# tester.net
KiCad netlist of a schematic drawn in EAGLE
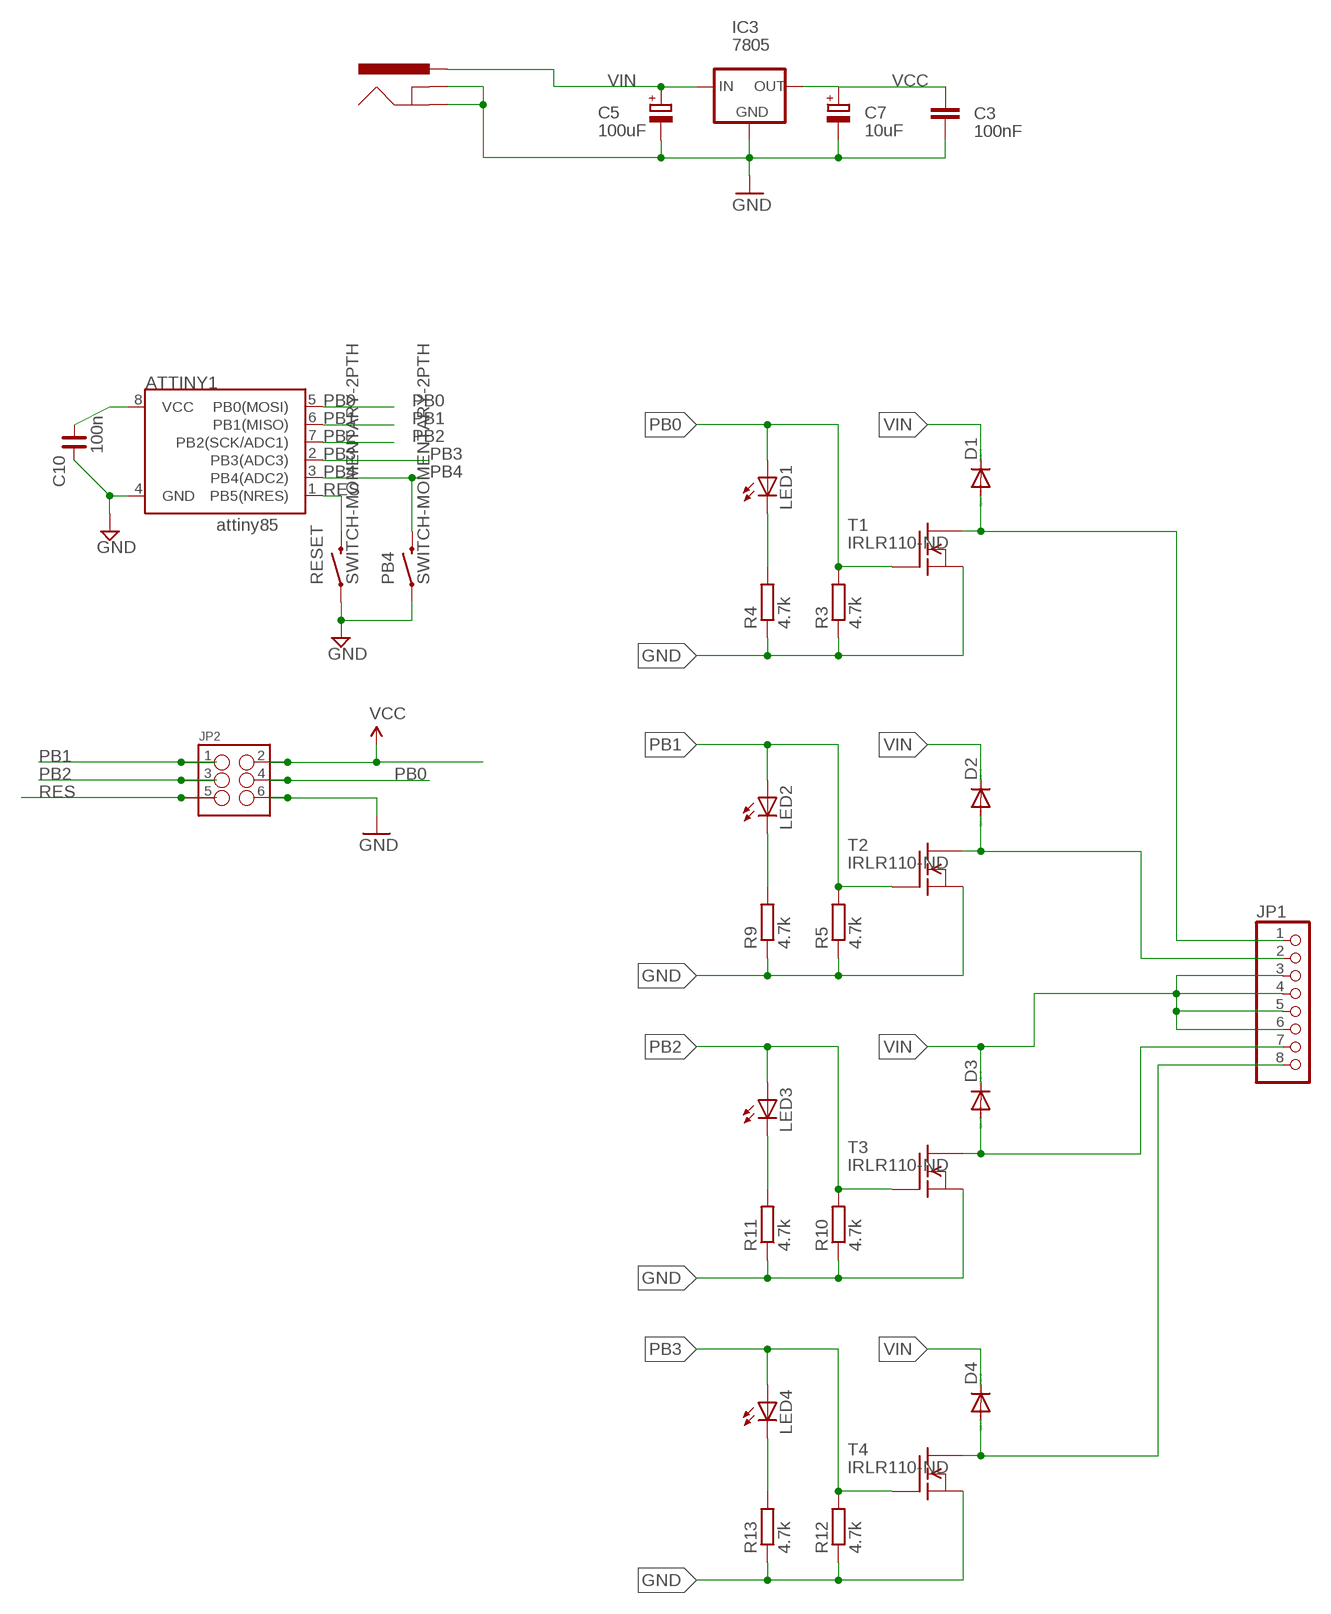
[diagram p0: schematic, sheet 1]

(export (version "E")
  (design (tool "Eeschema 10.0.6"))
  (components
    (comp (ref "ATTINY1")
      (value "ATTINY45DIP8")
      (footprint "eagle-import:DIP08")
      (libsource (lib "eagle-import") (part "ATTINY45DIP8"))
    )
    (comp (ref "C3")
      (value "100nF")
      (footprint "eagle-import:C050-024X044")
      (libsource (lib "eagle-import") (part "C-EU050-024X044"))
    )
    (comp (ref "C5")
      (value "100uF")
      (footprint "eagle-import:E2,5-5")
      (libsource (lib "eagle-import") (part "CPOL-EUE2.5-5"))
    )
    (comp (ref "C7")
      (value "10uF")
      (footprint "eagle-import:E2,5-5")
      (libsource (lib "eagle-import") (part "CPOL-EUE2.5-5"))
    )
    (comp (ref "C10")
      (value "100n")
      (footprint "eagle-import:C0603")
      (libsource (lib "eagle-import") (part "C_0603"))
    )
    (comp (ref "D1")
      (value "DIODE-DO214AC")
      (footprint "eagle-import:DO214AC")
      (libsource (lib "eagle-import") (part "DIODE-DO214AC"))
    )
    (comp (ref "D2")
      (value "DIODE-DO214AC")
      (footprint "eagle-import:DO214AC")
      (libsource (lib "eagle-import") (part "DIODE-DO214AC"))
    )
    (comp (ref "D3")
      (value "DIODE-DO214AC")
      (footprint "eagle-import:DO214AC")
      (libsource (lib "eagle-import") (part "DIODE-DO214AC"))
    )
    (comp (ref "D4")
      (value "DIODE-DO214AC")
      (footprint "eagle-import:DO214AC")
      (libsource (lib "eagle-import") (part "DIODE-DO214AC"))
    )
    (comp (ref "IC3")
      (value "7805")
      (footprint "eagle-import:78XXL")
      (libsource (lib "eagle-import") (part "78XXL"))
    )
    (comp (ref "J16")
      (value "POWER_JACKPTH")
      (footprint "eagle-import:POWER_JACK_PTH")
      (libsource (lib "eagle-import") (part "POWER_JACKPTH"))
    )
    (comp (ref "JP1")
      (value "PINHD-1X8")
      (footprint "eagle-import:1X08")
      (libsource (lib "eagle-import") (part "PINHD-1X8"))
    )
    (comp (ref "JP2")
      (value "M03X2NO_SILK")
      (footprint "eagle-import:2X3-NS@1")
      (libsource (lib "eagle-import") (part "M03X2NO_SILK"))
    )
    (comp (ref "LED1")
      (value "LEDCHIPLED_1206")
      (footprint "eagle-import:CHIPLED_1206")
      (libsource (lib "eagle-import") (part "LEDCHIPLED_1206"))
    )
    (comp (ref "LED2")
      (value "LEDCHIPLED_1206")
      (footprint "eagle-import:CHIPLED_1206")
      (libsource (lib "eagle-import") (part "LEDCHIPLED_1206"))
    )
    (comp (ref "LED3")
      (value "LEDCHIPLED_1206")
      (footprint "eagle-import:CHIPLED_1206")
      (libsource (lib "eagle-import") (part "LEDCHIPLED_1206"))
    )
    (comp (ref "LED4")
      (value "LEDCHIPLED_1206")
      (footprint "eagle-import:CHIPLED_1206")
      (libsource (lib "eagle-import") (part "LEDCHIPLED_1206"))
    )
    (comp (ref "PB4")
      (value "SWITCH-MOMENTARY-2PTH")
      (footprint "eagle-import:TACTILE-PTH")
      (libsource (lib "eagle-import") (part "SWITCH-MOMENTARY-2PTH"))
    )
    (comp (ref "R3")
      (value "4.7k")
      (footprint "eagle-import:R0603")
      (libsource (lib "eagle-import") (part "R-EU_R0603"))
    )
    (comp (ref "R4")
      (value "4.7k")
      (footprint "eagle-import:R0603")
      (libsource (lib "eagle-import") (part "R-EU_R0603"))
    )
    (comp (ref "R5")
      (value "4.7k")
      (footprint "eagle-import:R0603")
      (libsource (lib "eagle-import") (part "R-EU_R0603"))
    )
    (comp (ref "R9")
      (value "4.7k")
      (footprint "eagle-import:R0603")
      (libsource (lib "eagle-import") (part "R-EU_R0603"))
    )
    (comp (ref "R10")
      (value "4.7k")
      (footprint "eagle-import:R0603")
      (libsource (lib "eagle-import") (part "R-EU_R0603"))
    )
    (comp (ref "R11")
      (value "4.7k")
      (footprint "eagle-import:R0603")
      (libsource (lib "eagle-import") (part "R-EU_R0603"))
    )
    (comp (ref "R12")
      (value "4.7k")
      (footprint "eagle-import:R0603")
      (libsource (lib "eagle-import") (part "R-EU_R0603"))
    )
    (comp (ref "R13")
      (value "4.7k")
      (footprint "eagle-import:R0603")
      (libsource (lib "eagle-import") (part "R-EU_R0603"))
    )
    (comp (ref "RESET")
      (value "SWITCH-MOMENTARY-2PTH")
      (footprint "eagle-import:TACTILE-PTH")
      (libsource (lib "eagle-import") (part "SWITCH-MOMENTARY-2PTH"))
    )
    (comp (ref "T1")
      (value "IRLR110-ND")
      (footprint "eagle-import:TO252")
      (libsource (lib "eagle-import") (part "IRLR110-ND"))
    )
    (comp (ref "T2")
      (value "IRLR110-ND")
      (footprint "eagle-import:TO252")
      (libsource (lib "eagle-import") (part "IRLR110-ND"))
    )
    (comp (ref "T3")
      (value "IRLR110-ND")
      (footprint "eagle-import:TO252")
      (libsource (lib "eagle-import") (part "IRLR110-ND"))
    )
    (comp (ref "T4")
      (value "IRLR110-ND")
      (footprint "eagle-import:TO252")
      (libsource (lib "eagle-import") (part "IRLR110-ND"))
    )
  )
  (nets
    (net (code "1") (name "/PB4") (class "Default")
      (node (ref "ATTINY1") (pin "3") (pinfunction "PB4(ADC2)_3") (pintype "bidirectional"))
      (node (ref "PB4") (pin "3") (pinfunction "2_3") (pintype "passive"))
    )
    (net (code "2") (name "/RES") (class "Default")
      (node (ref "ATTINY1") (pin "1") (pinfunction "PB5(NRES)_1") (pintype "bidirectional"))
      (node (ref "JP2") (pin "5") (pinfunction "5_5") (pintype "bidirectional"))
      (node (ref "RESET") (pin "3") (pinfunction "2_3") (pintype "passive"))
    )
    (net (code "3") (name "GND") (class "Default")
      (node (ref "ATTINY1") (pin "4") (pinfunction "GND_4") (pintype "bidirectional"))
      (node (ref "C10") (pin "2") (pinfunction "2_2") (pintype "passive"))
      (node (ref "C3") (pin "2") (pinfunction "2_2") (pintype "passive"))
      (node (ref "C5") (pin "-") (pinfunction "-_-") (pintype "passive"))
      (node (ref "C7") (pin "-") (pinfunction "-_-") (pintype "passive"))
      (node (ref "IC3") (pin "GND") (pinfunction "GND_GND") (pintype "input"))
      (node (ref "J16") (pin "GND") (pinfunction "GND_GND") (pintype "bidirectional"))
      (node (ref "J16") (pin "GNDBREAK") (pinfunction "GNDBREAK_GNDBREAK") (pintype "bidirectional"))
      (node (ref "JP2") (pin "6") (pinfunction "6_6") (pintype "bidirectional"))
      (node (ref "PB4") (pin "1") (pinfunction "1_1") (pintype "passive"))
      (node (ref "R10") (pin "1") (pinfunction "1_1") (pintype "passive"))
      (node (ref "R11") (pin "1") (pinfunction "1_1") (pintype "passive"))
      (node (ref "R12") (pin "1") (pinfunction "1_1") (pintype "passive"))
      (node (ref "R13") (pin "1") (pinfunction "1_1") (pintype "passive"))
      (node (ref "R3") (pin "1") (pinfunction "1_1") (pintype "passive"))
      (node (ref "R4") (pin "1") (pinfunction "1_1") (pintype "passive"))
      (node (ref "R5") (pin "1") (pinfunction "1_1") (pintype "passive"))
      (node (ref "R9") (pin "1") (pinfunction "1_1") (pintype "passive"))
      (node (ref "RESET") (pin "1") (pinfunction "1_1") (pintype "passive"))
      (node (ref "T1") (pin "2") (pinfunction "S_2") (pintype "passive"))
      (node (ref "T2") (pin "2") (pinfunction "S_2") (pintype "passive"))
      (node (ref "T3") (pin "2") (pinfunction "S_2") (pintype "passive"))
      (node (ref "T4") (pin "2") (pinfunction "S_2") (pintype "passive"))
    )
    (net (code "4") (name "Net-(LED1-PadC)") (class "Default")
      (node (ref "LED1") (pin "C") (pinfunction "C_C") (pintype "passive"))
      (node (ref "R4") (pin "2") (pinfunction "2_2") (pintype "passive"))
    )
    (net (code "5") (name "Net-(LED2-PadC)") (class "Default")
      (node (ref "LED2") (pin "C") (pinfunction "C_C") (pintype "passive"))
      (node (ref "R9") (pin "2") (pinfunction "2_2") (pintype "passive"))
    )
    (net (code "6") (name "Net-(LED3-PadC)") (class "Default")
      (node (ref "LED3") (pin "C") (pinfunction "C_C") (pintype "passive"))
      (node (ref "R11") (pin "2") (pinfunction "2_2") (pintype "passive"))
    )
    (net (code "7") (name "Net-(LED4-PadC)") (class "Default")
      (node (ref "LED4") (pin "C") (pinfunction "C_C") (pintype "passive"))
      (node (ref "R13") (pin "2") (pinfunction "2_2") (pintype "passive"))
    )
    (net (code "8") (name "Net-(T1-D)") (class "Default")
      (node (ref "D1") (pin "A") (pinfunction "A_A") (pintype "passive"))
      (node (ref "JP1") (pin "1") (pinfunction "1_1") (pintype "passive"))
      (node (ref "T1") (pin "3") (pinfunction "D_3") (pintype "passive"))
    )
    (net (code "9") (name "Net-(T2-D)") (class "Default")
      (node (ref "D2") (pin "A") (pinfunction "A_A") (pintype "passive"))
      (node (ref "JP1") (pin "2") (pinfunction "2_2") (pintype "passive"))
      (node (ref "T2") (pin "3") (pinfunction "D_3") (pintype "passive"))
    )
    (net (code "10") (name "Net-(T3-D)") (class "Default")
      (node (ref "D3") (pin "A") (pinfunction "A_A") (pintype "passive"))
      (node (ref "JP1") (pin "7") (pinfunction "7_7") (pintype "passive"))
      (node (ref "T3") (pin "3") (pinfunction "D_3") (pintype "passive"))
    )
    (net (code "11") (name "Net-(T4-D)") (class "Default")
      (node (ref "D4") (pin "A") (pinfunction "A_A") (pintype "passive"))
      (node (ref "JP1") (pin "8") (pinfunction "8_8") (pintype "passive"))
      (node (ref "T4") (pin "3") (pinfunction "D_3") (pintype "passive"))
    )
    (net (code "12") (name "PB0") (class "Default")
      (node (ref "ATTINY1") (pin "5") (pinfunction "PB0(MOSI)_5") (pintype "bidirectional"))
      (node (ref "JP2") (pin "4") (pinfunction "4_4") (pintype "bidirectional"))
      (node (ref "LED1") (pin "A") (pinfunction "A_A") (pintype "passive"))
      (node (ref "R3") (pin "2") (pinfunction "2_2") (pintype "passive"))
      (node (ref "T1") (pin "1") (pinfunction "G_1") (pintype "passive"))
    )
    (net (code "13") (name "PB1") (class "Default")
      (node (ref "ATTINY1") (pin "6") (pinfunction "PB1(MISO)_6") (pintype "bidirectional"))
      (node (ref "JP2") (pin "1") (pinfunction "1_1") (pintype "bidirectional"))
      (node (ref "LED2") (pin "A") (pinfunction "A_A") (pintype "passive"))
      (node (ref "R5") (pin "2") (pinfunction "2_2") (pintype "passive"))
      (node (ref "T2") (pin "1") (pinfunction "G_1") (pintype "passive"))
    )
    (net (code "14") (name "PB2") (class "Default")
      (node (ref "ATTINY1") (pin "7") (pinfunction "PB2(SCK/ADC1)_7") (pintype "bidirectional"))
      (node (ref "JP2") (pin "3") (pinfunction "3_3") (pintype "bidirectional"))
      (node (ref "LED3") (pin "A") (pinfunction "A_A") (pintype "passive"))
      (node (ref "R10") (pin "2") (pinfunction "2_2") (pintype "passive"))
      (node (ref "T3") (pin "1") (pinfunction "G_1") (pintype "passive"))
    )
    (net (code "15") (name "PB3") (class "Default")
      (node (ref "ATTINY1") (pin "2") (pinfunction "PB3(ADC3)_2") (pintype "bidirectional"))
      (node (ref "LED4") (pin "A") (pinfunction "A_A") (pintype "passive"))
      (node (ref "R12") (pin "2") (pinfunction "2_2") (pintype "passive"))
      (node (ref "T4") (pin "1") (pinfunction "G_1") (pintype "passive"))
    )
    (net (code "16") (name "VCC") (class "Default")
      (node (ref "ATTINY1") (pin "8") (pinfunction "VCC_8") (pintype "bidirectional"))
      (node (ref "C10") (pin "1") (pinfunction "1_1") (pintype "passive"))
      (node (ref "C3") (pin "1") (pinfunction "1_1") (pintype "passive"))
      (node (ref "C7") (pin "+") (pinfunction "+_+") (pintype "passive"))
      (node (ref "IC3") (pin "OUT") (pinfunction "OUT_OUT") (pintype "passive"))
      (node (ref "JP2") (pin "2") (pinfunction "2_2") (pintype "bidirectional"))
    )
    (net (code "17") (name "VIN") (class "Default")
      (node (ref "C5") (pin "+") (pinfunction "+_+") (pintype "passive"))
      (node (ref "D1") (pin "C") (pinfunction "C_C") (pintype "passive"))
      (node (ref "D2") (pin "C") (pinfunction "C_C") (pintype "passive"))
      (node (ref "D3") (pin "C") (pinfunction "C_C") (pintype "passive"))
      (node (ref "D4") (pin "C") (pinfunction "C_C") (pintype "passive"))
      (node (ref "IC3") (pin "IN") (pinfunction "IN_IN") (pintype "input"))
      (node (ref "J16") (pin "PWR") (pinfunction "PWR_PWR") (pintype "bidirectional"))
      (node (ref "JP1") (pin "3") (pinfunction "3_3") (pintype "passive"))
      (node (ref "JP1") (pin "4") (pinfunction "4_4") (pintype "passive"))
      (node (ref "JP1") (pin "5") (pinfunction "5_5") (pintype "passive"))
      (node (ref "JP1") (pin "6") (pinfunction "6_6") (pintype "passive"))
    )
  )
)
